# expansion-sn76489-kempton-sd-rev7.net
KiCad netlist of a schematic drawn in EAGLE
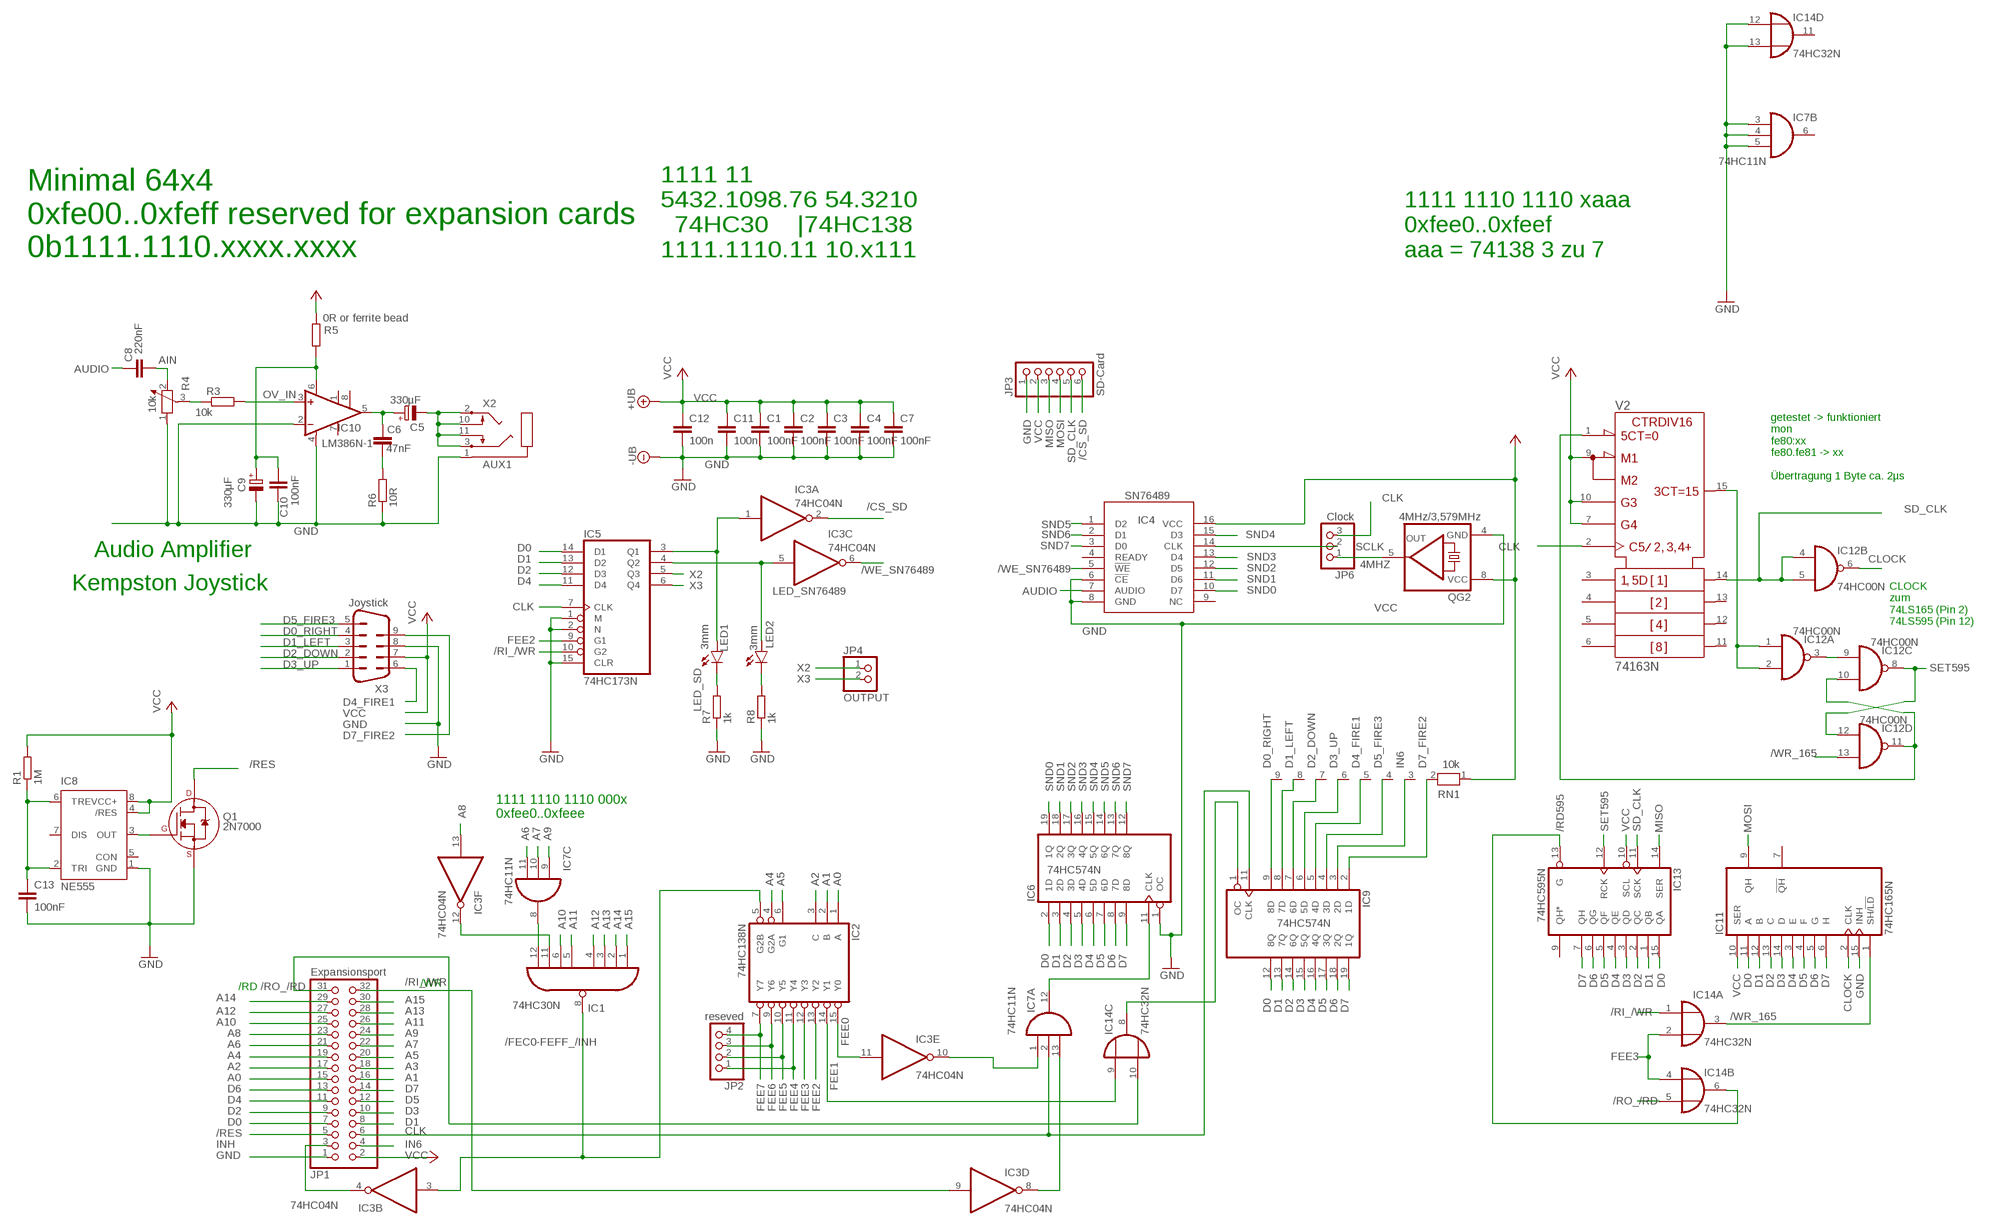
[diagram p0: schematic, sheet 1]

(export (version "E")
  (design (tool "Eeschema 10.0.6"))
  (components
    (comp (ref "C1")
      (value "100nF")
      (footprint "eagle-import:C050-025X075")
      (libsource (lib "eagle-import") (part "rcl_334_C-EU050-025X075"))
    )
    (comp (ref "C2")
      (value "100nF")
      (footprint "eagle-import:C050-025X075")
      (libsource (lib "eagle-import") (part "rcl_334_C-EU050-025X075"))
    )
    (comp (ref "C3")
      (value "100nF")
      (footprint "eagle-import:C050-025X075")
      (libsource (lib "eagle-import") (part "rcl_334_C-EU050-025X075"))
    )
    (comp (ref "C4")
      (value "100nF")
      (footprint "eagle-import:C050-025X075")
      (libsource (lib "eagle-import") (part "rcl_334_C-EU050-025X075"))
    )
    (comp (ref "C5")
      (value "330µF")
      (footprint "eagle-import:E2,5-7")
      (libsource (lib "eagle-import") (part "CPOL-EUE2.5-7"))
    )
    (comp (ref "C6")
      (value "47nF")
      (footprint "eagle-import:C050-025X075")
      (libsource (lib "eagle-import") (part "rcl_334_C-EU050-025X075"))
    )
    (comp (ref "C7")
      (value "100nF")
      (footprint "eagle-import:C050-025X075")
      (libsource (lib "eagle-import") (part "rcl_334_C-EU050-025X075"))
    )
    (comp (ref "C8")
      (value "220nF")
      (footprint "eagle-import:C050-025X075")
      (libsource (lib "eagle-import") (part "rcl_334_C-EU050-025X075"))
    )
    (comp (ref "C9")
      (value "330µF")
      (footprint "eagle-import:E2,5-7")
      (libsource (lib "eagle-import") (part "CPOL-EUE2.5-7"))
    )
    (comp (ref "C10")
      (value "100nF")
      (footprint "eagle-import:C050-025X075")
      (libsource (lib "eagle-import") (part "rcl_334_C-EU050-025X075"))
    )
    (comp (ref "C11")
      (value "100n")
      (footprint "eagle-import:C050-025X075")
      (libsource (lib "eagle-import") (part "rcl_334_C-EU050-025X075"))
    )
    (comp (ref "C12")
      (value "100n")
      (footprint "eagle-import:C050-025X075")
      (libsource (lib "eagle-import") (part "rcl_334_C-EU050-025X075"))
    )
    (comp (ref "C13")
      (value "100nF")
      (footprint "eagle-import:C050-030X075")
      (libsource (lib "eagle-import") (part "C-EU050-030X075"))
    )
    (comp (ref "IC1")
      (value "74HC30N")
      (footprint "eagle-import:DIL14")
      (libsource (lib "eagle-import") (part "7430NHC"))
    )
    (comp (ref "IC2")
      (value "74HC138N")
      (footprint "eagle-import:DIL16")
      (libsource (lib "eagle-import") (part "74138NHC"))
    )
    (comp (ref "IC3")
      (value "74HC04N")
      (footprint "eagle-import:DIL14")
      (libsource (lib "eagle-import") (part "7404NHC"))
    )
    (comp (ref "IC4")
      (value "SN76489")
      (footprint "eagle-import:ALEX-PARTS_DIL16")
      (libsource (lib "eagle-import") (part "ALEX-PARTS_SN76489AN"))
    )
    (comp (ref "IC5")
      (value "74HC173N")
      (footprint "eagle-import:DIL16")
      (libsource (lib "eagle-import") (part "74173NHC"))
    )
    (comp (ref "IC6")
      (value "74HC574N")
      (footprint "eagle-import:DIL20")
      (libsource (lib "eagle-import") (part "74574NHC"))
    )
    (comp (ref "IC7")
      (value "74HC11N")
      (footprint "eagle-import:DIL14")
      (libsource (lib "eagle-import") (part "7411NHC"))
    )
    (comp (ref "IC8")
      (value "NE555")
      (footprint "eagle-import:DIL-08")
      (libsource (lib "eagle-import") (part "NE555"))
    )
    (comp (ref "IC9")
      (value "74HC574N")
      (footprint "eagle-import:DIL20")
      (libsource (lib "eagle-import") (part "74574NHC"))
    )
    (comp (ref "IC10")
      (value "LM386N-1")
      (footprint "eagle-import:DIL08")
      (libsource (lib "eagle-import") (part "LM386?-N1"))
    )
    (comp (ref "IC11")
      (value "74HC165N")
      (footprint "eagle-import:DIL16")
      (libsource (lib "eagle-import") (part "74165NHC"))
    )
    (comp (ref "IC12")
      (value "74HC00N")
      (footprint "eagle-import:DIL14")
      (libsource (lib "eagle-import") (part "7400NHC"))
    )
    (comp (ref "IC13")
      (value "74HC595N")
      (footprint "eagle-import:DIL16")
      (libsource (lib "eagle-import") (part "74595NHC"))
    )
    (comp (ref "IC14")
      (value "74HC32N")
      (footprint "eagle-import:DIL14")
      (libsource (lib "eagle-import") (part "7432NHC"))
    )
    (comp (ref "JP1")
      (value "Expansionsport")
      (footprint "eagle-import:2X16")
      (libsource (lib "eagle-import") (part "PINHD-2X16"))
    )
    (comp (ref "JP2")
      (value "reseved")
      (footprint "eagle-import:1X04")
      (libsource (lib "eagle-import") (part "PINHD-1X4"))
    )
    (comp (ref "JP3")
      (value "SD-Card")
      (footprint "eagle-import:1X06")
      (libsource (lib "eagle-import") (part "PINHD-1X6"))
    )
    (comp (ref "JP4")
      (value "OUTPUT")
      (footprint "eagle-import:1X02")
      (libsource (lib "eagle-import") (part "PINHD-1X2"))
    )
    (comp (ref "JP6")
      (value "Clock")
      (footprint "eagle-import:1X03")
      (libsource (lib "eagle-import") (part "PINHD-1X3"))
    )
    (comp (ref "LED1")
      (value "3mm")
      (footprint "eagle-import:LED3MM")
      (libsource (lib "eagle-import") (part "LED3MM"))
    )
    (comp (ref "LED2")
      (value "3mm")
      (footprint "eagle-import:LED3MM")
      (libsource (lib "eagle-import") (part "LED3MM"))
    )
    (comp (ref "Q1")
      (value "2N7000")
      (footprint "eagle-import:TO-92")
      (libsource (lib "eagle-import") (part "2N700_TO920"))
    )
    (comp (ref "QG2")
      (value "4MHz/3,579MHz")
      (footprint "eagle-import:DIL08S")
      (libsource (lib "eagle-import") (part "QG5460"))
    )
    (comp (ref "R1")
      (value "1M")
      (footprint "eagle-import:0207_10")
      (libsource (lib "eagle-import") (part "R-EU_0207/10"))
    )
    (comp (ref "R3")
      (value "10k")
      (footprint "eagle-import:0207_10")
      (libsource (lib "eagle-import") (part "rcl_334_R-EU_0207/10"))
    )
    (comp (ref "R4")
      (value "10k")
      (footprint "eagle-import:PT-10S")
      (libsource (lib "eagle-import") (part "POTENTIOMETER_PT-10S"))
    )
    (comp (ref "R5")
      (value "0R or ferrite bead")
      (footprint "eagle-import:0207_10")
      (libsource (lib "eagle-import") (part "rcl_334_R-EU_0207/10"))
    )
    (comp (ref "R6")
      (value "10R")
      (footprint "eagle-import:0207_10")
      (libsource (lib "eagle-import") (part "rcl_334_R-EU_0207/10"))
    )
    (comp (ref "R7")
      (value "1k")
      (footprint "eagle-import:0207_2V")
      (libsource (lib "eagle-import") (part "rcl_334_R-EU_0207/2V"))
    )
    (comp (ref "R8")
      (value "1k")
      (footprint "eagle-import:0207_2V")
      (libsource (lib "eagle-import") (part "rcl_334_R-EU_0207/2V"))
    )
    (comp (ref "RN1")
      (value "10k")
      (footprint "eagle-import:RN-9")
      (libsource (lib "eagle-import") (part "RN08"))
    )
    (comp (ref "V2")
      (value "74163N")
      (footprint "eagle-import:DIL16")
      (libsource (lib "eagle-import") (part "74163N"))
    )
    (comp (ref "X2")
      (value "AUX1")
      (footprint "eagle-import:SJ1-352XN")
      (libsource (lib "eagle-import") (part "CON-SJ1-352XNSJ1-352XN"))
    )
    (comp (ref "X3")
      (value "Joystick")
      (footprint "eagle-import:182-009-MALE")
      (libsource (lib "eagle-import") (part "M09-182"))
    )
  )
  (nets
    (net (code "1") (name "+UB") (class "Default")
      (node (ref "C1") (pin "1") (pinfunction "1_1") (pintype "passive"))
      (node (ref "C11") (pin "1") (pinfunction "1_1") (pintype "passive"))
      (node (ref "C12") (pin "1") (pinfunction "1_1") (pintype "passive"))
      (node (ref "C2") (pin "1") (pinfunction "1_1") (pintype "passive"))
      (node (ref "C3") (pin "1") (pinfunction "1_1") (pintype "passive"))
      (node (ref "C4") (pin "1") (pinfunction "1_1") (pintype "passive"))
      (node (ref "C7") (pin "1") (pinfunction "1_1") (pintype "passive"))
      (node (ref "IC11") (pin "10") (pinfunction "SER_10") (pintype "input"))
      (node (ref "IC13") (pin "10") (pinfunction "SCL_10") (pintype "input"))
      (node (ref "IC4") (pin "16") (pinfunction "VCC_16") (pintype "input"))
      (node (ref "IC8") (pin "4") (pinfunction "/RES_4") (pintype "input"))
      (node (ref "IC8") (pin "8") (pinfunction "VCC+_8") (pintype "power_in"))
      (node (ref "JP1") (pin "2") (pinfunction "2_2") (pintype "passive"))
      (node (ref "JP3") (pin "2") (pinfunction "2_2") (pintype "passive"))
      (node (ref "QG2") (pin "8") (pinfunction "VCC_8") (pintype "power_in"))
      (node (ref "R1") (pin "2") (pinfunction "2_2") (pintype "passive"))
      (node (ref "R5") (pin "2") (pinfunction "2_2") (pintype "passive"))
      (node (ref "RN1") (pin "1") (pinfunction "1_1") (pintype "passive"))
      (node (ref "V2") (pin "10") (pinfunction "ENT_10") (pintype "input"))
      (node (ref "V2") (pin "7") (pinfunction "ENP_7") (pintype "input"))
      (node (ref "V2") (pin "9") (pinfunction "~{LOAD}_9") (pintype "input"))
      (node (ref "X3") (pin "7") (pinfunction "7_7") (pintype "passive"))
    )
    (net (code "2") (name "-UB") (class "Default")
      (node (ref "C1") (pin "2") (pinfunction "2_2") (pintype "passive"))
      (node (ref "C10") (pin "2") (pinfunction "2_2") (pintype "passive"))
      (node (ref "C11") (pin "2") (pinfunction "2_2") (pintype "passive"))
      (node (ref "C12") (pin "2") (pinfunction "2_2") (pintype "passive"))
      (node (ref "C13") (pin "2") (pinfunction "2_2") (pintype "passive"))
      (node (ref "C2") (pin "2") (pinfunction "2_2") (pintype "passive"))
      (node (ref "C3") (pin "2") (pinfunction "2_2") (pintype "passive"))
      (node (ref "C4") (pin "2") (pinfunction "2_2") (pintype "passive"))
      (node (ref "C7") (pin "2") (pinfunction "2_2") (pintype "passive"))
      (node (ref "C9") (pin "-") (pinfunction "-_-") (pintype "passive"))
      (node (ref "IC10") (pin "2") (pinfunction "-IN_2") (pintype "input"))
      (node (ref "IC10") (pin "4") (pinfunction "GND_4") (pintype "power_in"))
      (node (ref "IC11") (pin "15") (pinfunction "INH_15") (pintype "input"))
      (node (ref "IC14") (pin "12") (pinfunction "I0_12") (pintype "input"))
      (node (ref "IC14") (pin "13") (pinfunction "I1_13") (pintype "input"))
      (node (ref "IC4") (pin "6") (pinfunction "~{CE}_6") (pintype "input"))
      (node (ref "IC4") (pin "8") (pinfunction "GND_8") (pintype "power_in"))
      (node (ref "IC5") (pin "1") (pinfunction "M_1") (pintype "input"))
      (node (ref "IC5") (pin "15") (pinfunction "CLR_15") (pintype "input"))
      (node (ref "IC5") (pin "2") (pinfunction "N_2") (pintype "input"))
      (node (ref "IC6") (pin "1") (pinfunction "OC_1") (pintype "input"))
      (node (ref "IC7") (pin "3") (pinfunction "I0_3") (pintype "input"))
      (node (ref "IC7") (pin "4") (pinfunction "I1_4") (pintype "input"))
      (node (ref "IC7") (pin "5") (pinfunction "I2_5") (pintype "input"))
      (node (ref "IC8") (pin "1") (pinfunction "GND_1") (pintype "power_in"))
      (node (ref "JP1") (pin "1") (pinfunction "1_1") (pintype "passive"))
      (node (ref "JP3") (pin "1") (pinfunction "1_1") (pintype "passive"))
      (node (ref "Q1") (pin "1") (pinfunction "S_1") (pintype "bidirectional"))
      (node (ref "QG2") (pin "4") (pinfunction "GND_4") (pintype "power_in"))
      (node (ref "R4") (pin "1") (pinfunction "1_1") (pintype "passive"))
      (node (ref "R6") (pin "1") (pinfunction "1_1") (pintype "passive"))
      (node (ref "R7") (pin "1") (pinfunction "1_1") (pintype "passive"))
      (node (ref "R8") (pin "1") (pinfunction "1_1") (pintype "passive"))
      (node (ref "X2") (pin "1") (pinfunction "1_1") (pintype "passive"))
      (node (ref "X3") (pin "8") (pinfunction "8_8") (pintype "passive"))
    )
    (net (code "3") (name "/4MHZ") (class "Default")
      (node (ref "JP6") (pin "1") (pinfunction "1_1") (pintype "passive"))
      (node (ref "QG2") (pin "5") (pinfunction "OUT_5") (pintype "output"))
    )
    (net (code "4") (name "/A0") (class "Default")
      (node (ref "IC2") (pin "1") (pinfunction "A_1") (pintype "input"))
      (node (ref "JP1") (pin "15") (pinfunction "15_15") (pintype "passive"))
    )
    (net (code "5") (name "/A1") (class "Default")
      (node (ref "IC2") (pin "2") (pinfunction "B_2") (pintype "input"))
      (node (ref "JP1") (pin "16") (pinfunction "16_16") (pintype "passive"))
    )
    (net (code "6") (name "/A2") (class "Default")
      (node (ref "IC2") (pin "3") (pinfunction "C_3") (pintype "input"))
      (node (ref "JP1") (pin "17") (pinfunction "17_17") (pintype "passive"))
    )
    (net (code "7") (name "/A3") (class "Default")
      (node (ref "JP1") (pin "18") (pinfunction "18_18") (pintype "passive"))
    )
    (net (code "8") (name "/A4") (class "Default")
      (node (ref "IC2") (pin "4") (pinfunction "G2A_4") (pintype "input"))
      (node (ref "JP1") (pin "19") (pinfunction "19_19") (pintype "passive"))
    )
    (net (code "9") (name "/A5") (class "Default")
      (node (ref "IC2") (pin "6") (pinfunction "G1_6") (pintype "input"))
      (node (ref "JP1") (pin "20") (pinfunction "20_20") (pintype "passive"))
    )
    (net (code "10") (name "/A6") (class "Default")
      (node (ref "IC7") (pin "11") (pinfunction "I2_11") (pintype "input"))
      (node (ref "JP1") (pin "21") (pinfunction "21_21") (pintype "passive"))
    )
    (net (code "11") (name "/A7") (class "Default")
      (node (ref "IC7") (pin "10") (pinfunction "I1_10") (pintype "input"))
      (node (ref "JP1") (pin "22") (pinfunction "22_22") (pintype "passive"))
    )
    (net (code "12") (name "/A8") (class "Default")
      (node (ref "IC3") (pin "13") (pinfunction "I_13") (pintype "input"))
      (node (ref "JP1") (pin "23") (pinfunction "23_23") (pintype "passive"))
    )
    (net (code "13") (name "/A9") (class "Default")
      (node (ref "IC7") (pin "9") (pinfunction "I0_9") (pintype "input"))
      (node (ref "JP1") (pin "24") (pinfunction "24_24") (pintype "passive"))
    )
    (net (code "14") (name "/A10") (class "Default")
      (node (ref "IC1") (pin "6") (pinfunction "I5_6") (pintype "input"))
      (node (ref "JP1") (pin "25") (pinfunction "25_25") (pintype "passive"))
    )
    (net (code "15") (name "/A11") (class "Default")
      (node (ref "IC1") (pin "5") (pinfunction "I4_5") (pintype "input"))
      (node (ref "JP1") (pin "26") (pinfunction "26_26") (pintype "passive"))
    )
    (net (code "16") (name "/A12") (class "Default")
      (node (ref "IC1") (pin "4") (pinfunction "I3_4") (pintype "input"))
      (node (ref "JP1") (pin "27") (pinfunction "27_27") (pintype "passive"))
    )
    (net (code "17") (name "/A13") (class "Default")
      (node (ref "IC1") (pin "3") (pinfunction "I2_3") (pintype "input"))
      (node (ref "JP1") (pin "28") (pinfunction "28_28") (pintype "passive"))
    )
    (net (code "18") (name "/A14") (class "Default")
      (node (ref "IC1") (pin "2") (pinfunction "I1_2") (pintype "input"))
      (node (ref "JP1") (pin "29") (pinfunction "29_29") (pintype "passive"))
    )
    (net (code "19") (name "/A15") (class "Default")
      (node (ref "IC1") (pin "1") (pinfunction "I0_1") (pintype "input"))
      (node (ref "JP1") (pin "30") (pinfunction "30_30") (pintype "passive"))
    )
    (net (code "20") (name "/AIN") (class "Default")
      (node (ref "C8") (pin "2") (pinfunction "2_2") (pintype "passive"))
      (node (ref "R4") (pin "2") (pinfunction "2_2") (pintype "passive"))
    )
    (net (code "21") (name "/AUDIO") (class "Default")
      (node (ref "C8") (pin "1") (pinfunction "1_1") (pintype "passive"))
      (node (ref "IC4") (pin "7") (pinfunction "AUDIO_7") (pintype "output"))
    )
    (net (code "22") (name "/CLK") (class "Default")
      (node (ref "IC5") (pin "7") (pinfunction "CLK_7") (pintype "input"))
      (node (ref "IC7") (pin "2") (pinfunction "I1_2") (pintype "input"))
      (node (ref "IC9") (pin "11") (pinfunction "CLK_11") (pintype "input"))
      (node (ref "JP1") (pin "6") (pinfunction "6_6") (pintype "passive"))
      (node (ref "JP6") (pin "3") (pinfunction "3_3") (pintype "passive"))
      (node (ref "V2") (pin "2") (pinfunction "CLK_2") (pintype "input"))
    )
    (net (code "23") (name "/CLOCK") (class "Default")
      (node (ref "IC11") (pin "2") (pinfunction "CLK_2") (pintype "input"))
      (node (ref "IC12") (pin "6") (pinfunction "O_6") (pintype "output"))
    )
    (net (code "24") (name "/D0") (class "Default")
      (node (ref "IC11") (pin "11") (pinfunction "A_11") (pintype "input"))
      (node (ref "IC13") (pin "15") (pinfunction "QA_15") (pintype "tri_state"))
      (node (ref "IC5") (pin "14") (pinfunction "D1_14") (pintype "input"))
      (node (ref "IC6") (pin "2") (pinfunction "1D_2") (pintype "input"))
      (node (ref "IC9") (pin "12") (pinfunction "8Q_12") (pintype "tri_state"))
      (node (ref "JP1") (pin "7") (pinfunction "7_7") (pintype "passive"))
    )
    (net (code "25") (name "/D0_RIGHT") (class "Default")
      (node (ref "IC9") (pin "9") (pinfunction "8D_9") (pintype "input"))
      (node (ref "RN1") (pin "9") (pinfunction "9_9") (pintype "passive"))
      (node (ref "X3") (pin "4") (pinfunction "4_4") (pintype "passive"))
    )
    (net (code "26") (name "/D1") (class "Default")
      (node (ref "IC11") (pin "12") (pinfunction "B_12") (pintype "input"))
      (node (ref "IC13") (pin "1") (pinfunction "QB_1") (pintype "tri_state"))
      (node (ref "IC5") (pin "13") (pinfunction "D2_13") (pintype "input"))
      (node (ref "IC6") (pin "3") (pinfunction "2D_3") (pintype "input"))
      (node (ref "IC9") (pin "13") (pinfunction "7Q_13") (pintype "tri_state"))
      (node (ref "JP1") (pin "8") (pinfunction "8_8") (pintype "passive"))
    )
    (net (code "27") (name "/D1_LEFT") (class "Default")
      (node (ref "IC9") (pin "8") (pinfunction "7D_8") (pintype "input"))
      (node (ref "RN1") (pin "8") (pinfunction "8_8") (pintype "passive"))
      (node (ref "X3") (pin "3") (pinfunction "3_3") (pintype "passive"))
    )
    (net (code "28") (name "/D2") (class "Default")
      (node (ref "IC11") (pin "13") (pinfunction "C_13") (pintype "input"))
      (node (ref "IC13") (pin "2") (pinfunction "QC_2") (pintype "tri_state"))
      (node (ref "IC5") (pin "12") (pinfunction "D3_12") (pintype "input"))
      (node (ref "IC6") (pin "4") (pinfunction "3D_4") (pintype "input"))
      (node (ref "IC9") (pin "14") (pinfunction "6Q_14") (pintype "tri_state"))
      (node (ref "JP1") (pin "9") (pinfunction "9_9") (pintype "passive"))
    )
    (net (code "29") (name "/D2_DOWN") (class "Default")
      (node (ref "IC9") (pin "7") (pinfunction "6D_7") (pintype "input"))
      (node (ref "RN1") (pin "7") (pinfunction "7_7") (pintype "passive"))
      (node (ref "X3") (pin "2") (pinfunction "2_2") (pintype "passive"))
    )
    (net (code "30") (name "/D3") (class "Default")
      (node (ref "IC11") (pin "14") (pinfunction "D_14") (pintype "input"))
      (node (ref "IC13") (pin "3") (pinfunction "QD_3") (pintype "tri_state"))
      (node (ref "IC6") (pin "5") (pinfunction "4D_5") (pintype "input"))
      (node (ref "IC9") (pin "15") (pinfunction "5Q_15") (pintype "tri_state"))
      (node (ref "JP1") (pin "10") (pinfunction "10_10") (pintype "passive"))
    )
    (net (code "31") (name "/D3_UP") (class "Default")
      (node (ref "IC9") (pin "6") (pinfunction "5D_6") (pintype "input"))
      (node (ref "RN1") (pin "6") (pinfunction "6_6") (pintype "passive"))
      (node (ref "X3") (pin "1") (pinfunction "1_1") (pintype "passive"))
    )
    (net (code "32") (name "/D4") (class "Default")
      (node (ref "IC11") (pin "3") (pinfunction "E_3") (pintype "input"))
      (node (ref "IC13") (pin "4") (pinfunction "QE_4") (pintype "tri_state"))
      (node (ref "IC5") (pin "11") (pinfunction "D4_11") (pintype "input"))
      (node (ref "IC6") (pin "6") (pinfunction "5D_6") (pintype "input"))
      (node (ref "IC9") (pin "16") (pinfunction "4Q_16") (pintype "tri_state"))
      (node (ref "JP1") (pin "11") (pinfunction "11_11") (pintype "passive"))
    )
    (net (code "33") (name "/D4_FIRE1") (class "Default")
      (node (ref "IC9") (pin "5") (pinfunction "4D_5") (pintype "input"))
      (node (ref "RN1") (pin "5") (pinfunction "5_5") (pintype "passive"))
      (node (ref "X3") (pin "6") (pinfunction "6_6") (pintype "passive"))
    )
    (net (code "34") (name "/D5") (class "Default")
      (node (ref "IC11") (pin "4") (pinfunction "F_4") (pintype "input"))
      (node (ref "IC13") (pin "5") (pinfunction "QF_5") (pintype "tri_state"))
      (node (ref "IC6") (pin "7") (pinfunction "6D_7") (pintype "input"))
      (node (ref "IC9") (pin "17") (pinfunction "3Q_17") (pintype "tri_state"))
      (node (ref "JP1") (pin "12") (pinfunction "12_12") (pintype "passive"))
    )
    (net (code "35") (name "/D5_FIRE3") (class "Default")
      (node (ref "IC9") (pin "4") (pinfunction "3D_4") (pintype "input"))
      (node (ref "RN1") (pin "4") (pinfunction "4_4") (pintype "passive"))
      (node (ref "X3") (pin "5") (pinfunction "5_5") (pintype "passive"))
    )
    (net (code "36") (name "/D6") (class "Default")
      (node (ref "IC11") (pin "5") (pinfunction "G_5") (pintype "input"))
      (node (ref "IC13") (pin "6") (pinfunction "QG_6") (pintype "tri_state"))
      (node (ref "IC6") (pin "8") (pinfunction "7D_8") (pintype "input"))
      (node (ref "IC9") (pin "18") (pinfunction "2Q_18") (pintype "tri_state"))
      (node (ref "JP1") (pin "13") (pinfunction "13_13") (pintype "passive"))
    )
    (net (code "37") (name "/D7") (class "Default")
      (node (ref "IC11") (pin "6") (pinfunction "H_6") (pintype "input"))
      (node (ref "IC13") (pin "7") (pinfunction "QH_7") (pintype "tri_state"))
      (node (ref "IC6") (pin "9") (pinfunction "8D_9") (pintype "input"))
      (node (ref "IC9") (pin "19") (pinfunction "1Q_19") (pintype "tri_state"))
      (node (ref "JP1") (pin "14") (pinfunction "14_14") (pintype "passive"))
    )
    (net (code "38") (name "/D7_FIRE2") (class "Default")
      (node (ref "IC9") (pin "2") (pinfunction "1D_2") (pintype "input"))
      (node (ref "RN1") (pin "2") (pinfunction "2_2") (pintype "passive"))
      (node (ref "X3") (pin "9") (pinfunction "9_9") (pintype "passive"))
    )
    (net (code "39") (name "/FEE0") (class "Default")
      (node (ref "IC2") (pin "15") (pinfunction "Y0_15") (pintype "output"))
      (node (ref "IC3") (pin "11") (pinfunction "I_11") (pintype "input"))
    )
    (net (code "40") (name "/FEE1") (class "Default")
      (node (ref "IC14") (pin "9") (pinfunction "I0_9") (pintype "input"))
      (node (ref "IC2") (pin "14") (pinfunction "Y1_14") (pintype "output"))
    )
    (net (code "41") (name "/FEE2") (class "Default")
      (node (ref "IC2") (pin "13") (pinfunction "Y2_13") (pintype "output"))
      (node (ref "IC5") (pin "9") (pinfunction "G1_9") (pintype "input"))
    )
    (net (code "42") (name "/FEE3") (class "Default")
      (node (ref "IC14") (pin "2") (pinfunction "I1_2") (pintype "input"))
      (node (ref "IC14") (pin "4") (pinfunction "I0_4") (pintype "input"))
      (node (ref "IC2") (pin "12") (pinfunction "Y3_12") (pintype "output"))
    )
    (net (code "43") (name "/FEE4") (class "Default")
      (node (ref "IC2") (pin "11") (pinfunction "Y4_11") (pintype "output"))
      (node (ref "JP2") (pin "1") (pinfunction "1_1") (pintype "passive"))
    )
    (net (code "44") (name "/FEE5") (class "Default")
      (node (ref "IC2") (pin "10") (pinfunction "Y5_10") (pintype "output"))
      (node (ref "JP2") (pin "2") (pinfunction "2_2") (pintype "passive"))
    )
    (net (code "45") (name "/FEE6") (class "Default")
      (node (ref "IC2") (pin "9") (pinfunction "Y6_9") (pintype "output"))
      (node (ref "JP2") (pin "3") (pinfunction "3_3") (pintype "passive"))
    )
    (net (code "46") (name "/FEE7") (class "Default")
      (node (ref "IC2") (pin "7") (pinfunction "Y7_7") (pintype "output"))
      (node (ref "JP2") (pin "4") (pinfunction "4_4") (pintype "passive"))
    )
    (net (code "47") (name "/IN6") (class "Default")
      (node (ref "IC9") (pin "3") (pinfunction "2D_3") (pintype "input"))
      (node (ref "JP1") (pin "4") (pinfunction "4_4") (pintype "passive"))
      (node (ref "RN1") (pin "3") (pinfunction "3_3") (pintype "passive"))
    )
    (net (code "48") (name "/INH") (class "Default")
      (node (ref "IC3") (pin "4") (pinfunction "O_4") (pintype "output"))
      (node (ref "JP1") (pin "3") (pinfunction "3_3") (pintype "passive"))
    )
    (net (code "49") (name "/LED_SD") (class "Default")
      (node (ref "IC3") (pin "1") (pinfunction "I_1") (pintype "input"))
      (node (ref "IC5") (pin "3") (pinfunction "Q1_3") (pintype "tri_state"))
      (node (ref "LED1") (pin "A") (pinfunction "A_A") (pintype "passive"))
    )
    (net (code "50") (name "/LED_SN76489") (class "Default")
      (node (ref "IC3") (pin "5") (pinfunction "I_5") (pintype "input"))
      (node (ref "IC5") (pin "4") (pinfunction "Q2_4") (pintype "tri_state"))
      (node (ref "LED2") (pin "A") (pinfunction "A_A") (pintype "passive"))
    )
    (net (code "51") (name "/MISO") (class "Default")
      (node (ref "IC13") (pin "14") (pinfunction "SER_14") (pintype "input"))
      (node (ref "JP3") (pin "3") (pinfunction "3_3") (pintype "passive"))
    )
    (net (code "52") (name "/MOSI") (class "Default")
      (node (ref "IC11") (pin "9") (pinfunction "QH_9") (pintype "output"))
      (node (ref "JP3") (pin "4") (pinfunction "4_4") (pintype "passive"))
    )
    (net (code "53") (name "/OV_IN") (class "Default")
      (node (ref "IC10") (pin "3") (pinfunction "+IN_3") (pintype "input"))
      (node (ref "R3") (pin "2") (pinfunction "2_2") (pintype "passive"))
    )
    (net (code "54") (name "/SCLK") (class "Default")
      (node (ref "IC4") (pin "14") (pinfunction "CLK_14") (pintype "input"))
      (node (ref "JP6") (pin "2") (pinfunction "2_2") (pintype "passive"))
    )
    (net (code "55") (name "/SD_CLK") (class "Default")
      (node (ref "IC12") (pin "4") (pinfunction "I0_4") (pintype "input"))
      (node (ref "IC12") (pin "5") (pinfunction "I1_5") (pintype "input"))
      (node (ref "IC13") (pin "11") (pinfunction "SCK_11") (pintype "input"))
      (node (ref "JP3") (pin "5") (pinfunction "5_5") (pintype "passive"))
      (node (ref "V2") (pin "14") (pinfunction "QA_14") (pintype "output"))
    )
    (net (code "56") (name "/SET595") (class "Default")
      (node (ref "IC12") (pin "12") (pinfunction "I0_12") (pintype "input"))
      (node (ref "IC12") (pin "8") (pinfunction "O_8") (pintype "output"))
      (node (ref "IC13") (pin "12") (pinfunction "RCK_12") (pintype "input"))
    )
    (net (code "57") (name "/SND0") (class "Default")
      (node (ref "IC4") (pin "10") (pinfunction "D7_10") (pintype "input"))
      (node (ref "IC6") (pin "19") (pinfunction "1Q_19") (pintype "tri_state"))
    )
    (net (code "58") (name "/SND1") (class "Default")
      (node (ref "IC4") (pin "11") (pinfunction "D6_11") (pintype "input"))
      (node (ref "IC6") (pin "18") (pinfunction "2Q_18") (pintype "tri_state"))
    )
    (net (code "59") (name "/SND2") (class "Default")
      (node (ref "IC4") (pin "12") (pinfunction "D5_12") (pintype "input"))
      (node (ref "IC6") (pin "17") (pinfunction "3Q_17") (pintype "tri_state"))
    )
    (net (code "60") (name "/SND3") (class "Default")
      (node (ref "IC4") (pin "13") (pinfunction "D4_13") (pintype "input"))
      (node (ref "IC6") (pin "16") (pinfunction "4Q_16") (pintype "tri_state"))
    )
    (net (code "61") (name "/SND4") (class "Default")
      (node (ref "IC4") (pin "15") (pinfunction "D3_15") (pintype "input"))
      (node (ref "IC6") (pin "15") (pinfunction "5Q_15") (pintype "tri_state"))
    )
    (net (code "62") (name "/SND5") (class "Default")
      (node (ref "IC4") (pin "1") (pinfunction "D2_1") (pintype "input"))
      (node (ref "IC6") (pin "14") (pinfunction "6Q_14") (pintype "tri_state"))
    )
    (net (code "63") (name "/SND6") (class "Default")
      (node (ref "IC4") (pin "2") (pinfunction "D1_2") (pintype "input"))
      (node (ref "IC6") (pin "13") (pinfunction "7Q_13") (pintype "tri_state"))
    )
    (net (code "64") (name "/SND7") (class "Default")
      (node (ref "IC4") (pin "3") (pinfunction "D0_3") (pintype "input"))
      (node (ref "IC6") (pin "12") (pinfunction "8Q_12") (pintype "tri_state"))
    )
    (net (code "65") (name "/X2") (class "Default")
      (node (ref "IC5") (pin "5") (pinfunction "Q3_5") (pintype "tri_state"))
      (node (ref "JP4") (pin "1") (pinfunction "1_1") (pintype "passive"))
    )
    (net (code "66") (name "/X3") (class "Default")
      (node (ref "IC5") (pin "6") (pinfunction "Q4_6") (pintype "tri_state"))
      (node (ref "JP4") (pin "2") (pinfunction "2_2") (pintype "passive"))
    )
    (net (code "67") (name "/{slash}CS_SD") (class "Default")
      (node (ref "IC3") (pin "2") (pinfunction "O_2") (pintype "output"))
      (node (ref "JP3") (pin "6") (pinfunction "6_6") (pintype "passive"))
    )
    (net (code "68") (name "/{slash}FEC0-FEFF_{slash}INH") (class "Default")
      (node (ref "IC1") (pin "8") (pinfunction "O_8") (pintype "output"))
      (node (ref "IC2") (pin "5") (pinfunction "G2B_5") (pintype "input"))
      (node (ref "IC3") (pin "3") (pinfunction "I_3") (pintype "input"))
    )
    (net (code "69") (name "/{slash}RD595") (class "Default")
      (node (ref "IC13") (pin "13") (pinfunction "G_13") (pintype "input"))
      (node (ref "IC14") (pin "6") (pinfunction "O_6") (pintype "output"))
    )
    (net (code "70") (name "/{slash}RES") (class "Default")
      (node (ref "JP1") (pin "5") (pinfunction "5_5") (pintype "passive"))
      (node (ref "Q1") (pin "3") (pinfunction "D_3") (pintype "bidirectional"))
    )
    (net (code "71") (name "/{slash}RI_{slash}WR") (class "Default")
      (node (ref "IC14") (pin "1") (pinfunction "I0_1") (pintype "input"))
      (node (ref "IC3") (pin "9") (pinfunction "I_9") (pintype "input"))
      (node (ref "IC5") (pin "10") (pinfunction "G2_10") (pintype "input"))
      (node (ref "JP1") (pin "32") (pinfunction "32_32") (pintype "passive"))
    )
    (net (code "72") (name "/{slash}RO_{slash}RD") (class "Default")
      (node (ref "IC14") (pin "10") (pinfunction "I1_10") (pintype "input"))
      (node (ref "IC14") (pin "5") (pinfunction "I1_5") (pintype "input"))
      (node (ref "JP1") (pin "31") (pinfunction "31_31") (pintype "passive"))
    )
    (net (code "73") (name "/{slash}WE_SN76489") (class "Default")
      (node (ref "IC3") (pin "6") (pinfunction "O_6") (pintype "output"))
      (node (ref "IC4") (pin "5") (pinfunction "~{WE}_5") (pintype "input"))
    )
    (net (code "74") (name "/{slash}WR_165") (class "Default")
      (node (ref "IC11") (pin "1") (pinfunction "SH/~{LD}_1") (pintype "input"))
      (node (ref "IC12") (pin "13") (pinfunction "I1_13") (pintype "input"))
      (node (ref "IC14") (pin "3") (pinfunction "O_3") (pintype "output"))
    )
    (net (code "75") (name "Net-(C5-Pad-)") (class "Default")
      (node (ref "C5") (pin "-") (pinfunction "-_-") (pintype "passive"))
      (node (ref "X2") (pin "10") (pinfunction "10_10") (pintype "passive"))
      (node (ref "X2") (pin "11") (pinfunction "11_11") (pintype "passive"))
      (node (ref "X2") (pin "2") (pinfunction "2_2") (pintype "passive"))
      (node (ref "X2") (pin "3") (pinfunction "3_3") (pintype "passive"))
    )
    (net (code "76") (name "Net-(C6-Pad2)") (class "Default")
      (node (ref "C6") (pin "2") (pinfunction "2_2") (pintype "passive"))
      (node (ref "R6") (pin "2") (pinfunction "2_2") (pintype "passive"))
    )
    (net (code "77") (name "Net-(IC1A-I6)") (class "Default")
      (node (ref "IC1") (pin "11") (pinfunction "I6_11") (pintype "input"))
      (node (ref "IC3") (pin "12") (pinfunction "O_12") (pintype "output"))
    )
    (net (code "78") (name "Net-(IC1A-I7)") (class "Default")
      (node (ref "IC1") (pin "12") (pinfunction "I7_12") (pintype "input"))
      (node (ref "IC7") (pin "8") (pinfunction "O_8") (pintype "output"))
    )
    (net (code "79") (name "Net-(IC3D-O)") (class "Default")
      (node (ref "IC3") (pin "8") (pinfunction "O_8") (pintype "output"))
      (node (ref "IC7") (pin "13") (pinfunction "I2_13") (pintype "input"))
    )
    (net (code "80") (name "Net-(IC3E-O)") (class "Default")
      (node (ref "IC3") (pin "10") (pinfunction "O_10") (pintype "output"))
      (node (ref "IC7") (pin "1") (pinfunction "I0_1") (pintype "input"))
    )
    (net (code "81") (name "Net-(IC6A-CLK)") (class "Default")
      (node (ref "IC6") (pin "11") (pinfunction "CLK_11") (pintype "input"))
      (node (ref "IC7") (pin "12") (pinfunction "O_12") (pintype "output"))
    )
    (net (code "82") (name "Net-(IC8-OUT)") (class "Default")
      (node (ref "IC8") (pin "3") (pinfunction "OUT_3") (pintype "output"))
      (node (ref "Q1") (pin "2") (pinfunction "G_2") (pintype "tri_state"))
    )
    (net (code "83") (name "Net-(IC8-TRE)") (class "Default")
      (node (ref "C13") (pin "1") (pinfunction "1_1") (pintype "passive"))
      (node (ref "IC8") (pin "2") (pinfunction "TRI_2") (pintype "input"))
      (node (ref "IC8") (pin "6") (pinfunction "TRE_6") (pintype "input"))
      (node (ref "R1") (pin "1") (pinfunction "1_1") (pintype "passive"))
    )
    (net (code "84") (name "Net-(IC10-OUT)") (class "Default")
      (node (ref "C5") (pin "+") (pinfunction "+_+") (pintype "passive"))
      (node (ref "C6") (pin "1") (pinfunction "1_1") (pintype "passive"))
      (node (ref "IC10") (pin "5") (pinfunction "OUT_5") (pintype "output"))
    )
    (net (code "85") (name "Net-(IC10-VS)") (class "Default")
      (node (ref "C10") (pin "1") (pinfunction "1_1") (pintype "passive"))
      (node (ref "C9") (pin "+") (pinfunction "+_+") (pintype "passive"))
      (node (ref "IC10") (pin "6") (pinfunction "VS_6") (pintype "power_in"))
      (node (ref "R5") (pin "1") (pinfunction "1_1") (pintype "passive"))
    )
    (net (code "86") (name "Net-(IC12A-I0)") (class "Default")
      (node (ref "IC12") (pin "1") (pinfunction "I0_1") (pintype "input"))
      (node (ref "IC12") (pin "2") (pinfunction "I1_2") (pintype "input"))
      (node (ref "V2") (pin "15") (pinfunction "RCO_15") (pintype "output"))
    )
    (net (code "87") (name "Net-(IC12A-O)") (class "Default")
      (node (ref "IC12") (pin "3") (pinfunction "O_3") (pintype "output"))
      (node (ref "IC12") (pin "9") (pinfunction "I0_9") (pintype "input"))
    )
    (net (code "88") (name "Net-(IC12C-I1)") (class "Default")
      (node (ref "IC12") (pin "10") (pinfunction "I1_10") (pintype "input"))
      (node (ref "IC12") (pin "11") (pinfunction "O_11") (pintype "output"))
      (node (ref "V2") (pin "1") (pinfunction "~{CLR}_1") (pintype "input"))
    )
    (net (code "89") (name "Net-(IC14C-O)") (class "Default")
      (node (ref "IC14") (pin "8") (pinfunction "O_8") (pintype "output"))
      (node (ref "IC9") (pin "1") (pinfunction "OC_1") (pintype "input"))
    )
    (net (code "90") (name "Net-(LED1-C)") (class "Default")
      (node (ref "LED1") (pin "K") (pinfunction "C_K") (pintype "passive"))
      (node (ref "R7") (pin "2") (pinfunction "2_2") (pintype "passive"))
    )
    (net (code "91") (name "Net-(LED2-C)") (class "Default")
      (node (ref "LED2") (pin "K") (pinfunction "C_K") (pintype "passive"))
      (node (ref "R8") (pin "2") (pinfunction "2_2") (pintype "passive"))
    )
    (net (code "92") (name "Net-(R3-Pad1)") (class "Default")
      (node (ref "R3") (pin "1") (pinfunction "1_1") (pintype "passive"))
      (node (ref "R4") (pin "3") (pinfunction "3_3") (pintype "passive"))
    )
    (net (code "93") (name "unconnected-(IC4-NC-Pad9)") (class "Default")
      (node (ref "IC4") (pin "9") (pinfunction "NC_9") (pintype "no_connect"))
    )
    (net (code "94") (name "unconnected-(IC4-READY-Pad4)") (class "Default")
      (node (ref "IC4") (pin "4") (pinfunction "READY_4") (pintype "output"))
    )
    (net (code "95") (name "unconnected-(IC7B-O-Pad6)") (class "Default")
      (node (ref "IC7") (pin "6") (pinfunction "O_6") (pintype "output"))
    )
    (net (code "96") (name "unconnected-(IC8-CON-Pad5)") (class "Default")
      (node (ref "IC8") (pin "5") (pinfunction "CON_5") (pintype "input"))
    )
    (net (code "97") (name "unconnected-(IC8-DIS-Pad7)") (class "Default")
      (node (ref "IC8") (pin "7") (pinfunction "DIS_7") (pintype "input"))
    )
    (net (code "98") (name "unconnected-(IC10-BYPASS-Pad7)") (class "Default")
      (node (ref "IC10") (pin "7") (pinfunction "BYPASS_7") (pintype "passive"))
    )
    (net (code "99") (name "unconnected-(IC10-GAIN-Pad1)") (class "Default")
      (node (ref "IC10") (pin "1") (pinfunction "GAIN_1") (pintype "passive"))
    )
    (net (code "100") (name "unconnected-(IC10-GAIN-Pad8)") (class "Default")
      (node (ref "IC10") (pin "8") (pinfunction "GAIN_8") (pintype "passive"))
    )
    (net (code "101") (name "unconnected-(IC11A-~{QH}-Pad7)") (class "Default")
      (node (ref "IC11") (pin "7") (pinfunction "~{QH}_7") (pintype "output"))
    )
    (net (code "102") (name "unconnected-(IC13A-QH*-Pad9)") (class "Default")
      (node (ref "IC13") (pin "9") (pinfunction "QH*_9") (pintype "tri_state"))
    )
    (net (code "103") (name "unconnected-(IC14D-O-Pad11)") (class "Default")
      (node (ref "IC14") (pin "11") (pinfunction "O_11") (pintype "output"))
    )
    (net (code "104") (name "unconnected-(V2C-A-Pad3)") (class "Default")
      (node (ref "V2") (pin "3") (pinfunction "A_3") (pintype "input"))
    )
    (net (code "105") (name "unconnected-(V2C-B-Pad4)") (class "Default")
      (node (ref "V2") (pin "4") (pinfunction "B_4") (pintype "input"))
    )
    (net (code "106") (name "unconnected-(V2C-C-Pad5)") (class "Default")
      (node (ref "V2") (pin "5") (pinfunction "C_5") (pintype "input"))
    )
    (net (code "107") (name "unconnected-(V2C-D-Pad6)") (class "Default")
      (node (ref "V2") (pin "6") (pinfunction "D_6") (pintype "input"))
    )
    (net (code "108") (name "unconnected-(V2C-QB-Pad13)") (class "Default")
      (node (ref "V2") (pin "13") (pinfunction "QB_13") (pintype "output"))
    )
    (net (code "109") (name "unconnected-(V2C-QC-Pad12)") (class "Default")
      (node (ref "V2") (pin "12") (pinfunction "QC_12") (pintype "output"))
    )
    (net (code "110") (name "unconnected-(V2C-QD-Pad11)") (class "Default")
      (node (ref "V2") (pin "11") (pinfunction "QD_11") (pintype "output"))
    )
  )
)
